# Sheet1.net
KiCad netlist of a schematic drawn in Altium Designer
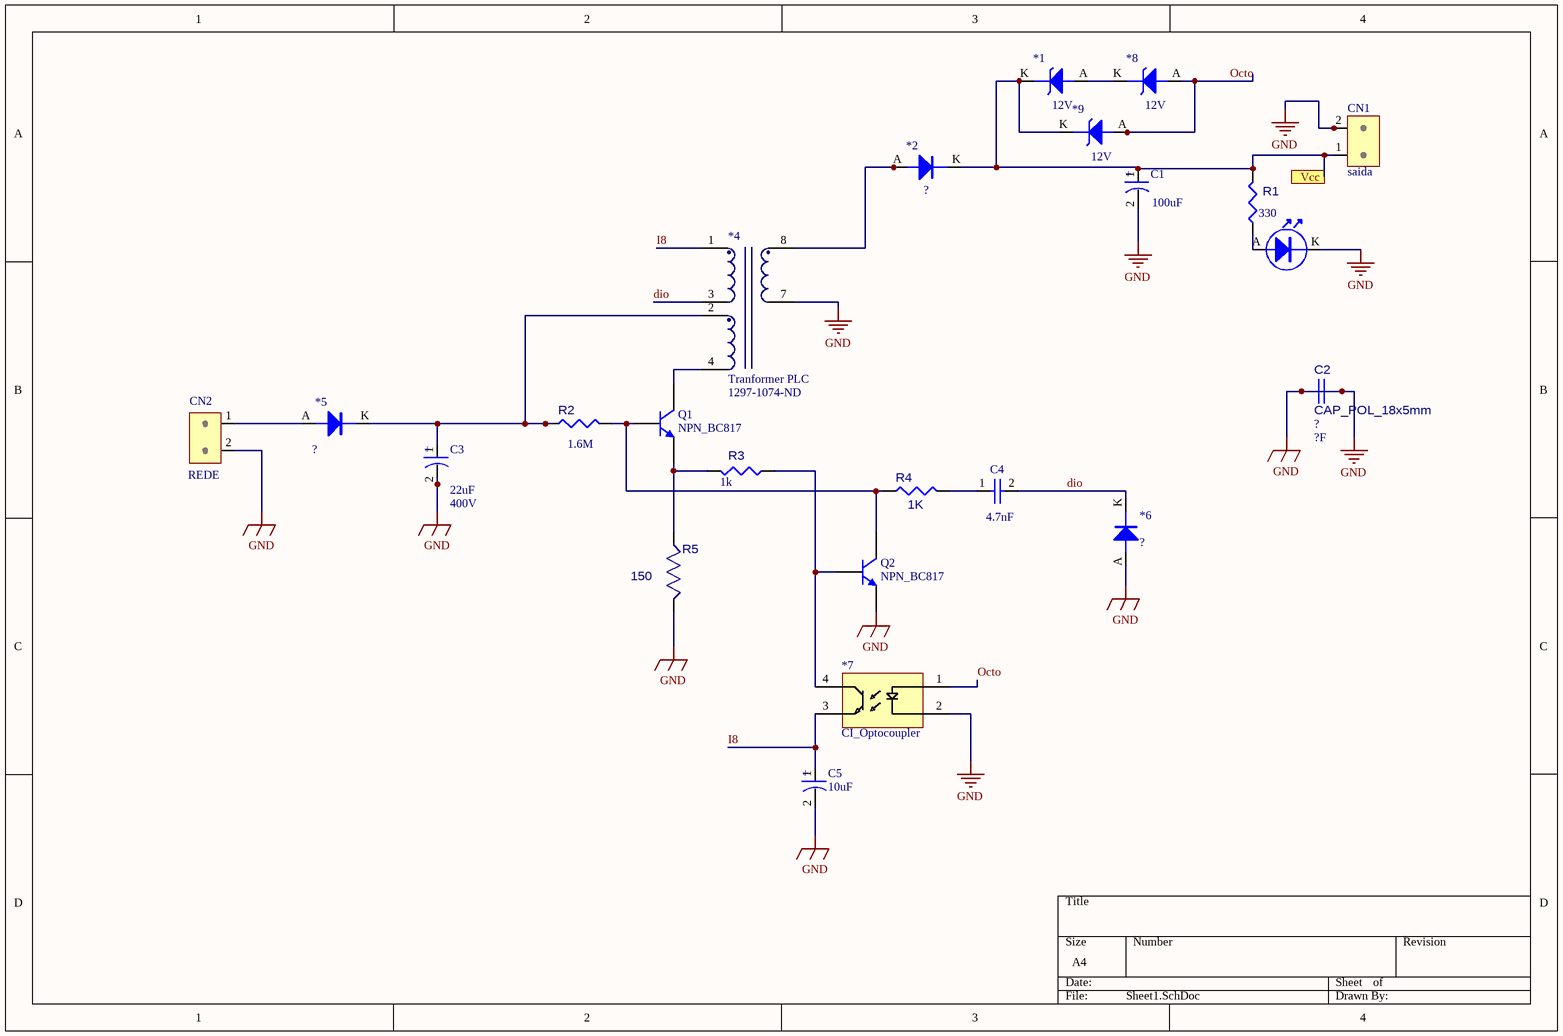
[diagram p0: Sheet1.SchDoc]

(export (version "E")
  (design (tool "Eeschema 10.0.6"))
  (components
    (comp (ref "*1")
      (value "12V")
      (footprint "DIO_PTH_DO35")
      (fields (field (name "Comment") "DIO_ZENER_DO35"))
      (libsource (lib "i9Library_Altium") (part "DIO_ZENER_DO35"))
    )
    (comp (ref "*2")
      (value "?")
      (footprint "DIO_PTH_DO41")
      (fields (field (name "Comment") "DIO_PTH_1N4007"))
      (libsource (lib "i9Library_Altium") (part "DIO_PTH_1N4007"))
    )
    (comp (ref "*3")
      (value "LED_AXIAL_5MM")
      (footprint "LED_Axial_5mm")
      (libsource (lib "i9Library_Altium") (part "LED_AXIAL_5MM"))
    )
    (comp (ref "*4")
      (value "Tranformer PLC")
      (footprint "DIV_TRAFO PLC")
      (fields (field (name "SUPPLIER PART NUMBER 1") "1297-1074-ND"))
      (libsource (lib "i9Library_Altium") (part "Tranformer PLC"))
    )
    (comp (ref "*5")
      (value "?")
      (footprint "DIO_PTH_DO41")
      (fields (field (name "Comment") "DIO_SMD_1N4148"))
      (libsource (lib "i9Library_Altium") (part "DIO_SMD_1N4148"))
    )
    (comp (ref "*6")
      (value "?")
      (footprint "DIO_PTH_DO41")
      (fields (field (name "Comment") "DIO_PTH_1N4007"))
      (libsource (lib "i9Library_Altium") (part "DIO_PTH_1N4007"))
    )
    (comp (ref "*7")
      (value "CI_Optocoupler")
      (footprint "SFH6106")
      (libsource (lib "i9Library_Altium") (part "CI_Optocoupler"))
    )
    (comp (ref "*8")
      (value "12V")
      (footprint "DIO_PTH_DO35")
      (fields (field (name "Comment") "DIO_ZENER_DO35"))
      (libsource (lib "i9Library_Altium") (part "DIO_ZENER_DO35"))
    )
    (comp (ref "*9")
      (value "12V")
      (footprint "DIO_PTH_DO35")
      (fields (field (name "Comment") "DIO_ZENER_DO35"))
      (libsource (lib "i9Library_Altium") (part "DIO_ZENER_DO35"))
    )
    (comp (ref "C1")
      (value "100uF")
      (footprint "CAP_ALU_RADIAL_5MM")
      (description "PTH Radial Electrolytic Capacitor")
      (fields (field (name "Comment") "Electrolytic Capacitor"))
      (libsource (lib "i9Library_Altium") (part "CAP_ALU_RADIAL_5MM"))
    )
    (comp (ref "C2")
      (value "?F")
      (footprint "CAP_POL_18x5mm")
      (description "SMD Ceramic Capacitor")
      (fields (field (name "TENSÃO") "?"))
      (libsource (lib "i9Library_Altium") (part "CAP_CER_POLI_18x5mm"))
    )
    (comp (ref "C3")
      (value "22uF")
      (footprint "CAP_ALU_RADIAL_5MM")
      (description "PTH Radial Electrolytic Capacitor")
      (fields (field (name "TENSÃO") "400V") (field (name "Comment") "Electrolytic Capacitor"))
      (libsource (lib "i9Library_Altium") (part "CAP_ALU_RADIAL_5MM"))
    )
    (comp (ref "C4")
      (value "4.7nF")
      (footprint "CAP_POL_RADIAL_16MM")
      (description "PTH Radial Polyester Capacitor")
      (fields (field (name "Comment") "CAP_POL_RADIAL_16MM"))
      (libsource (lib "i9Library_Altium") (part "CAP_POL_RADIAL_16MM"))
    )
    (comp (ref "C5")
      (value "10uF")
      (footprint "CAP_ALU_RADIAL_5MM")
      (description "PTH Radial Electrolytic Capacitor")
      (libsource (lib "i9Library_Altium") (part "CAP_ALU_RADIAL_5MM"))
    )
    (comp (ref "CN1")
      (value "saida")
      (footprint "CN_KRE_2")
      (description "MKDS_2")
      (libsource (lib "") (part "CN_MKDS_2_1"))
    )
    (comp (ref "CN2")
      (value "?")
      (footprint "REDE")
      (description "MKDS_2")
      (libsource (lib "i9Library_Altium") (part "CN_MKDS_2"))
    )
    (comp (ref "Q1")
      (value "NPN_BC817")
      (footprint "HEADER_1X3")
      (libsource (lib "i9Library_Altium") (part "NPN_BC817"))
    )
    (comp (ref "Q2")
      (value "NPN_BC817")
      (footprint "HEADER_1X3")
      (libsource (lib "i9Library_Altium") (part "NPN_BC817"))
    )
    (comp (ref "R1")
      (value "330")
      (footprint "RES_PTH_7.62MM")
      (description "Pin Through Hole Resistor 7.62mm")
      (libsource (lib "i9Library_Altium") (part "RES_PTH_7.62MM"))
    )
    (comp (ref "R2")
      (value "1.6M")
      (footprint "RES_PTH_7.62MM")
      (description "Pin Through Hole Resistor 7.62mm")
      (libsource (lib "i9Library_Altium") (part "RES_PTH_7.62MM"))
    )
    (comp (ref "R3")
      (value "1k")
      (footprint "RES_PTH_7.62MM")
      (description "Pin Through Hole Resistor 7.62mm")
      (libsource (lib "i9Library_Altium") (part "RES_PTH_7.62MM"))
    )
    (comp (ref "R4")
      (value "?")
      (footprint "1K")
      (description "Pin Through Hole Resistor 7.62mm")
      (libsource (lib "i9Library_Altium") (part "RES_PTH_7.62MM"))
    )
    (comp (ref "R5")
      (value "*")
      (footprint "150")
      (description "Pin Through Hole Resistor 300mils/7.62mm")
      (libsource (lib "i9Library_v1.7.5") (part "RES_PTH300"))
    )
  )
  (nets
    (net (code "1") (name "/I8") (class "Default")
      (node (ref "*4") (pin "1") (pinfunction "1_1") (pintype "passive"))
      (node (ref "*7") (pin "3") (pinfunction "C_3") (pintype "passive"))
      (node (ref "C5") (pin "1") (pinfunction "1_1") (pintype "passive"))
    )
    (net (code "2") (name "/Octo") (class "Default")
      (node (ref "*7") (pin "1") (pinfunction "A_1") (pintype "passive"))
      (node (ref "*8") (pin "A") (pintype "passive"))
      (node (ref "*9") (pin "A") (pintype "passive"))
    )
    (net (code "3") (name "/Vcc") (class "Default")
      (node (ref "*1") (pin "K") (pintype "passive"))
      (node (ref "*2") (pin "K") (pintype "passive"))
      (node (ref "*9") (pin "K") (pintype "passive"))
      (node (ref "C1") (pin "1") (pinfunction "1_1") (pintype "passive"))
      (node (ref "CN1") (pin "1") (pintype "passive"))
      (node (ref "R1") (pin "2") (pinfunction "2_2") (pintype "passive"))
    )
    (net (code "4") (name "/dio") (class "Default")
      (node (ref "*4") (pin "3") (pinfunction "3_3") (pintype "passive"))
      (node (ref "*6") (pin "K") (pintype "passive"))
      (node (ref "C4") (pin "2") (pintype "passive"))
    )
    (net (code "5") (name "GND") (class "Default")
      (node (ref "*3") (pin "K") (pintype "passive"))
      (node (ref "*4") (pin "7") (pinfunction "7_7") (pintype "passive"))
      (node (ref "*6") (pin "A") (pintype "passive"))
      (node (ref "*7") (pin "2") (pinfunction "C_2") (pintype "passive"))
      (node (ref "C1") (pin "2") (pintype "passive"))
      (node (ref "C2") (pin "1") (pintype "passive"))
      (node (ref "C2") (pin "2") (pintype "passive"))
      (node (ref "C3") (pin "2") (pintype "passive"))
      (node (ref "C5") (pin "2") (pintype "passive"))
      (node (ref "CN1") (pin "2") (pinfunction "2_2") (pintype "passive"))
      (node (ref "CN2") (pin "2") (pinfunction "2_2") (pintype "passive"))
      (node (ref "Q2") (pin "2") (pinfunction "E_2") (pintype "passive"))
      (node (ref "R5") (pin "2") (pintype "passive"))
    )
    (net (code "6") (name "Net-(*1-PadA)") (class "Default")
      (node (ref "*1") (pin "A") (pintype "passive"))
      (node (ref "*8") (pin "K") (pintype "passive"))
    )
    (net (code "7") (name "Net-(*2-PadA)") (class "Default")
      (node (ref "*2") (pin "A") (pintype "passive"))
      (node (ref "*4") (pin "8") (pinfunction "8_8") (pintype "passive"))
    )
    (net (code "8") (name "Net-(*3-PadA)") (class "Default")
      (node (ref "*3") (pin "A") (pintype "passive"))
      (node (ref "R1") (pin "1") (pinfunction "1_1") (pintype "passive"))
    )
    (net (code "9") (name "Net-(*4-Pad2)") (class "Default")
      (node (ref "*4") (pin "2") (pinfunction "2_2") (pintype "passive"))
      (node (ref "*5") (pin "K") (pintype "passive"))
      (node (ref "C3") (pin "1") (pinfunction "1_1") (pintype "passive"))
      (node (ref "R2") (pin "1") (pinfunction "1_1") (pintype "passive"))
    )
    (net (code "10") (name "Net-(*5-PadA)") (class "Default")
      (node (ref "*5") (pin "A") (pintype "passive"))
      (node (ref "CN2") (pin "1") (pintype "passive"))
    )
    (net (code "11") (name "Net-(*7-E)") (class "Default")
      (node (ref "*7") (pin "4") (pinfunction "E_4") (pintype "passive"))
      (node (ref "Q2") (pin "1") (pinfunction "B_1") (pintype "passive"))
      (node (ref "R3") (pin "1") (pinfunction "1_1") (pintype "passive"))
    )
    (net (code "12") (name "Net-(C4-Pad1)") (class "Default")
      (node (ref "C4") (pin "1") (pintype "passive"))
      (node (ref "R4") (pin "2") (pinfunction "2_2") (pintype "passive"))
    )
    (net (code "13") (name "Net-(Q1-B)") (class "Default")
      (node (ref "Q1") (pin "1") (pinfunction "B_1") (pintype "passive"))
      (node (ref "Q2") (pin "3") (pinfunction "C_3") (pintype "passive"))
      (node (ref "R2") (pin "2") (pinfunction "2_2") (pintype "passive"))
      (node (ref "R4") (pin "1") (pinfunction "1_1") (pintype "passive"))
    )
    (net (code "14") (name "Net-(Q1-C)") (class "Default")
      (node (ref "*4") (pin "4") (pinfunction "4_4") (pintype "passive"))
      (node (ref "Q1") (pin "3") (pinfunction "C_3") (pintype "passive"))
    )
    (net (code "15") (name "Net-(Q1-E)") (class "Default")
      (node (ref "Q1") (pin "2") (pinfunction "E_2") (pintype "passive"))
      (node (ref "R3") (pin "2") (pinfunction "2_2") (pintype "passive"))
      (node (ref "R5") (pin "1") (pintype "passive"))
    )
  )
)
